# PAM2320_Breakout.net
KiCad netlist of a schematic drawn in EAGLE
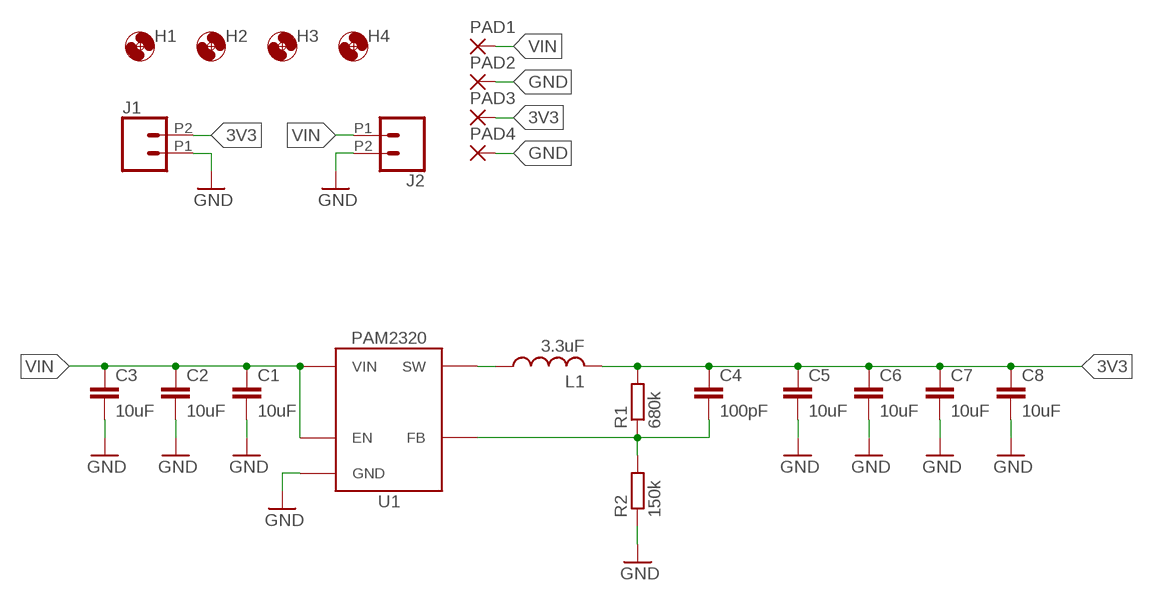
[diagram p0: schematic, sheet 1]

(export (version "E")
  (design (tool "Eeschema 10.0.6"))
  (components
    (comp (ref "C1")
      (value "10uF")
      (footprint "eagle-import:C0805")
      (fields (field (name "MF") "Murata") (field (name "MPN") "GRM21BR61C106KE15K"))
      (libsource (lib "eagle-import") (part "C-EUC080510UF"))
    )
    (comp (ref "C2")
      (value "10uF")
      (footprint "eagle-import:C0805")
      (fields (field (name "MF") "Murata") (field (name "MPN") "GRM21BR61C106KE15K"))
      (libsource (lib "eagle-import") (part "C-EUC080510UF"))
    )
    (comp (ref "C3")
      (value "10uF")
      (footprint "eagle-import:C0805")
      (fields (field (name "MF") "Murata") (field (name "MPN") "GRM21BR61C106KE15K"))
      (libsource (lib "eagle-import") (part "C-EUC080510UF"))
    )
    (comp (ref "C4")
      (value "100pF")
      (footprint "eagle-import:C0603")
      (libsource (lib "eagle-import") (part "C-EUC0603"))
    )
    (comp (ref "C5")
      (value "10uF")
      (footprint "eagle-import:C0805")
      (fields (field (name "MF") "Murata") (field (name "MPN") "GRM21BR61C106KE15K"))
      (libsource (lib "eagle-import") (part "C-EUC080510UF"))
    )
    (comp (ref "C6")
      (value "10uF")
      (footprint "eagle-import:C0805")
      (fields (field (name "MF") "Murata") (field (name "MPN") "GRM21BR61C106KE15K"))
      (libsource (lib "eagle-import") (part "C-EUC080510UF"))
    )
    (comp (ref "C7")
      (value "10uF")
      (footprint "eagle-import:C0805")
      (fields (field (name "MF") "Murata") (field (name "MPN") "GRM21BR61C106KE15K"))
      (libsource (lib "eagle-import") (part "C-EUC080510UF"))
    )
    (comp (ref "C8")
      (value "10uF")
      (footprint "eagle-import:C0805")
      (fields (field (name "MF") "Murata") (field (name "MPN") "GRM21BR61C106KE15K"))
      (libsource (lib "eagle-import") (part "C-EUC080510UF"))
    )
    (comp (ref "H1")
      (value "MOUNTING_HOLE2_NP")
      (footprint "eagle-import:2_56")
      (fields (field (name "MPN") "DNP"))
      (libsource (lib "eagle-import") (part "MOUNTING_HOLE2_NP"))
    )
    (comp (ref "H2")
      (value "MOUNTING_HOLE2_NP")
      (footprint "eagle-import:2_56")
      (fields (field (name "MPN") "DNP"))
      (libsource (lib "eagle-import") (part "MOUNTING_HOLE2_NP"))
    )
    (comp (ref "H3")
      (value "MOUNTING_HOLE2_NP")
      (footprint "eagle-import:2_56")
      (fields (field (name "MPN") "DNP"))
      (libsource (lib "eagle-import") (part "MOUNTING_HOLE2_NP"))
    )
    (comp (ref "H4")
      (value "MOUNTING_HOLE2_NP")
      (footprint "eagle-import:2_56")
      (fields (field (name "MPN") "DNP"))
      (libsource (lib "eagle-import") (part "MOUNTING_HOLE2_NP"))
    )
    (comp (ref "J1")
      (value "CONN_022.54_SCREW_ROUND")
      (footprint "eagle-import:1X02_2.54_SCREWTERM_ROUND")
      (fields (field (name "MF") "OnShore") (field (name "MPN") "OSTVN02A150"))
      (libsource (lib "eagle-import") (part "CONN_022.54_SCREW_ROUND"))
    )
    (comp (ref "J2")
      (value "CONN_022.54_SCREW_ROUND")
      (footprint "eagle-import:1X02_2.54_SCREWTERM_ROUND")
      (fields (field (name "MF") "OnShore") (field (name "MPN") "OSTVN02A150"))
      (libsource (lib "eagle-import") (part "CONN_022.54_SCREW_ROUND"))
    )
    (comp (ref "L1")
      (value "3.3uF")
      (footprint "eagle-import:WE-MAPI(5.4X5.4)")
      (libsource (lib "eagle-import") (part "INDUCTOR_MAPI_5.4X5.4"))
    )
    (comp (ref "PAD1")
      (value "SMD5")
      (footprint "eagle-import:SMD2,54-5,08")
      (libsource (lib "eagle-import") (part "SMD5"))
    )
    (comp (ref "PAD2")
      (value "SMD5")
      (footprint "eagle-import:SMD2,54-5,08")
      (libsource (lib "eagle-import") (part "SMD5"))
    )
    (comp (ref "PAD3")
      (value "SMD5")
      (footprint "eagle-import:SMD2,54-5,08")
      (libsource (lib "eagle-import") (part "SMD5"))
    )
    (comp (ref "PAD4")
      (value "SMD5")
      (footprint "eagle-import:SMD2,54-5,08")
      (libsource (lib "eagle-import") (part "SMD5"))
    )
    (comp (ref "R1")
      (value "680k")
      (footprint "eagle-import:R0603")
      (fields (field (name "MF") "Yageo"))
      (libsource (lib "eagle-import") (part "R-EU_R0603"))
    )
    (comp (ref "R2")
      (value "150k")
      (footprint "eagle-import:R0603")
      (fields (field (name "MF") "Yageo"))
      (libsource (lib "eagle-import") (part "R-EU_R0603"))
    )
    (comp (ref "U1")
      (value "PAM2320")
      (footprint "eagle-import:PSOP-8")
      (fields (field (name "MF") "Diodes Inc") (field (name "MPN") "PAM2320BECADJR"))
      (libsource (lib "eagle-import") (part "PAM2320"))
    )
  )
  (nets
    (net (code "1") (name "3V3") (class "Default")
      (node (ref "C4") (pin "1") (pinfunction "1_1") (pintype "passive"))
      (node (ref "C5") (pin "1") (pinfunction "1_1") (pintype "passive"))
      (node (ref "C6") (pin "1") (pinfunction "1_1") (pintype "passive"))
      (node (ref "C7") (pin "1") (pinfunction "1_1") (pintype "passive"))
      (node (ref "C8") (pin "1") (pinfunction "1_1") (pintype "passive"))
      (node (ref "J1") (pin "P2") (pinfunction "2_P2") (pintype "passive"))
      (node (ref "L1") (pin "P$2") (pinfunction "2_P$2") (pintype "passive"))
      (node (ref "PAD3") (pin "1") (pinfunction "P_1") (pintype "passive"))
      (node (ref "R1") (pin "2") (pinfunction "2_2") (pintype "passive"))
    )
    (net (code "2") (name "GND") (class "Default")
      (node (ref "C1") (pin "2") (pinfunction "2_2") (pintype "passive"))
      (node (ref "C2") (pin "2") (pinfunction "2_2") (pintype "passive"))
      (node (ref "C3") (pin "2") (pinfunction "2_2") (pintype "passive"))
      (node (ref "C5") (pin "2") (pinfunction "2_2") (pintype "passive"))
      (node (ref "C6") (pin "2") (pinfunction "2_2") (pintype "passive"))
      (node (ref "C7") (pin "2") (pinfunction "2_2") (pintype "passive"))
      (node (ref "C8") (pin "2") (pinfunction "2_2") (pintype "passive"))
      (node (ref "J1") (pin "P1") (pinfunction "1_P1") (pintype "passive"))
      (node (ref "J2") (pin "P2") (pinfunction "2_P2") (pintype "passive"))
      (node (ref "PAD2") (pin "1") (pinfunction "P_1") (pintype "passive"))
      (node (ref "PAD4") (pin "1") (pinfunction "P_1") (pintype "passive"))
      (node (ref "R2") (pin "1") (pinfunction "1_1") (pintype "passive"))
      (node (ref "U1") (pin "4") (pinfunction "GND_4") (pintype "power_in"))
      (node (ref "U1") (pin "EP") (pinfunction "GND_EP") (pintype "power_in"))
    )
    (net (code "3") (name "Net-(L1-1)") (class "Default")
      (node (ref "L1") (pin "P$1") (pinfunction "1_P$1") (pintype "passive"))
      (node (ref "U1") (pin "3") (pinfunction "SW_3") (pintype "power_in"))
    )
    (net (code "4") (name "Net-(U1-FB)") (class "Default")
      (node (ref "C4") (pin "2") (pinfunction "2_2") (pintype "passive"))
      (node (ref "R1") (pin "1") (pinfunction "1_1") (pintype "passive"))
      (node (ref "R2") (pin "2") (pinfunction "2_2") (pintype "passive"))
      (node (ref "U1") (pin "5") (pinfunction "FB_5") (pintype "input"))
    )
    (net (code "5") (name "VIN") (class "Default")
      (node (ref "C1") (pin "1") (pinfunction "1_1") (pintype "passive"))
      (node (ref "C2") (pin "1") (pinfunction "1_1") (pintype "passive"))
      (node (ref "C3") (pin "1") (pinfunction "1_1") (pintype "passive"))
      (node (ref "J2") (pin "P1") (pinfunction "1_P1") (pintype "passive"))
      (node (ref "PAD1") (pin "1") (pinfunction "P_1") (pintype "passive"))
      (node (ref "U1") (pin "2") (pinfunction "VIN_2") (pintype "power_in"))
      (node (ref "U1") (pin "7") (pinfunction "EN_7") (pintype "input"))
    )
  )
)
